# speaker-board.net
KiCad netlist of a schematic drawn in EAGLE
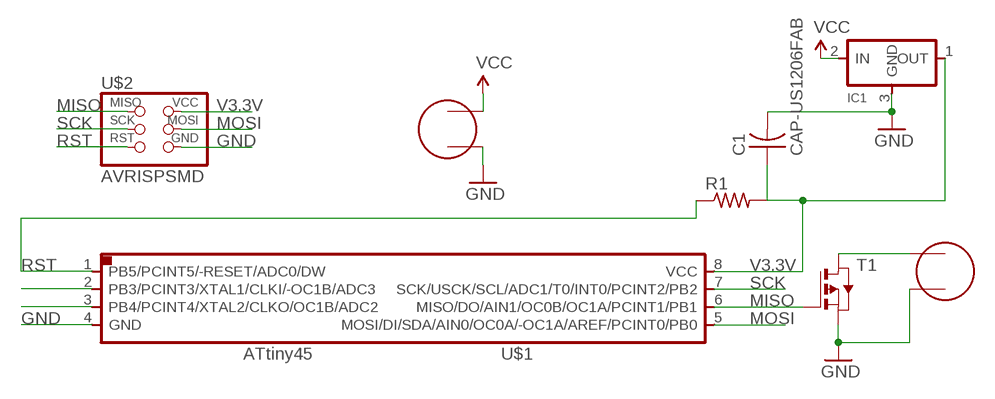
[diagram p0: schematic, sheet 1]

(export (version "E")
  (design (tool "Eeschema 10.0.6"))
  (components
    (comp (ref "C1")
      (value "CAP-US1206FAB")
      (footprint "eagle-import:C1206FAB")
      (libsource (lib "eagle-import") (part "CAP-US1206FAB"))
    )
    (comp (ref "IC1")
      (value "REGULATORSOT23")
      (footprint "eagle-import:SOT23")
      (libsource (lib "eagle-import") (part "REGULATORSOT23"))
    )
    (comp (ref "R1")
      (value "RES-US1206FAB")
      (footprint "eagle-import:R1206FAB")
      (libsource (lib "eagle-import") (part "RES-US1206FAB"))
    )
    (comp (ref "T1")
      (value "PMOSFETSOT23")
      (footprint "eagle-import:SOT-23")
      (libsource (lib "eagle-import") (part "PMOSFETSOT23"))
    )
    (comp (ref "U$1")
      (value "ATTINY45SI")
      (footprint "eagle-import:SOIC8")
      (libsource (lib "eagle-import") (part "ATTINY45SI"))
    )
    (comp (ref "U$2")
      (value "AVRISPSMD")
      (footprint "eagle-import:2X03SMD")
      (libsource (lib "eagle-import") (part "AVRISPSMD"))
    )
    (comp (ref "U$3")
      (value "PINHD-2X1-SMD")
      (footprint "eagle-import:2X01SMD")
      (libsource (lib "eagle-import") (part "PINHD-2X1-SMD"))
    )
    (comp (ref "U$4")
      (value "PINHD-2X1-SMD")
      (footprint "eagle-import:2X01SMD")
      (libsource (lib "eagle-import") (part "PINHD-2X1-SMD"))
    )
  )
  (nets
    (net (code "1") (name "/MISO") (class "Default")
      (node (ref "T1") (pin "3") (pinfunction "G_3") (pintype "passive"))
      (node (ref "U$1") (pin "6") (pinfunction "MISO/DO/AIN1/OC0B/OC1A/PCINT1/PB1_6") (pintype "bidirectional"))
      (node (ref "U$2") (pin "1") (pinfunction "MISO_1") (pintype "passive"))
    )
    (net (code "2") (name "/MOSI") (class "Default")
      (node (ref "U$1") (pin "5") (pinfunction "MOSI/DI/SDA/AIN0/OC0A/-OC1A/AREF/PCINT0/PB0_5") (pintype "bidirectional"))
      (node (ref "U$2") (pin "4") (pinfunction "MOSI_4") (pintype "passive"))
    )
    (net (code "3") (name "/RST") (class "Default")
      (node (ref "R1") (pin "1") (pinfunction "1_1") (pintype "passive"))
      (node (ref "U$1") (pin "1") (pinfunction "PB5/PCINT5/-RESET/ADC0/DW_1") (pintype "bidirectional"))
      (node (ref "U$2") (pin "5") (pinfunction "RST_5") (pintype "passive"))
    )
    (net (code "4") (name "/SCK") (class "Default")
      (node (ref "U$1") (pin "7") (pinfunction "SCK/USCK/SCL/ADC1/T0/INT0/PCINT2/PB2_7") (pintype "bidirectional"))
      (node (ref "U$2") (pin "3") (pinfunction "SCK_3") (pintype "passive"))
    )
    (net (code "5") (name "/V3.3V") (class "Default")
      (node (ref "C1") (pin "1") (pinfunction "1_1") (pintype "passive"))
      (node (ref "IC1") (pin "1") (pinfunction "OUT_1") (pintype "bidirectional"))
      (node (ref "R1") (pin "2") (pinfunction "2_2") (pintype "passive"))
      (node (ref "U$1") (pin "8") (pinfunction "VCC_8") (pintype "bidirectional"))
      (node (ref "U$2") (pin "2") (pinfunction "VCC_2") (pintype "passive"))
    )
    (net (code "6") (name "GND") (class "Default")
      (node (ref "C1") (pin "2") (pinfunction "2_2") (pintype "passive"))
      (node (ref "IC1") (pin "3") (pinfunction "GND_3") (pintype "bidirectional"))
      (node (ref "T1") (pin "2") (pinfunction "S_2") (pintype "passive"))
      (node (ref "U$1") (pin "4") (pinfunction "GND_4") (pintype "bidirectional"))
      (node (ref "U$2") (pin "6") (pinfunction "GND_6") (pintype "passive"))
      (node (ref "U$3") (pin "4") (pinfunction "P$2_4") (pintype "bidirectional"))
      (node (ref "U$4") (pin "3") (pinfunction "P$1_3") (pintype "bidirectional"))
    )
    (net (code "7") (name "Net-(T1-D)") (class "Default")
      (node (ref "T1") (pin "1") (pinfunction "D_1") (pintype "passive"))
      (node (ref "U$3") (pin "3") (pinfunction "P$1_3") (pintype "bidirectional"))
    )
    (net (code "8") (name "VCC") (class "Default")
      (node (ref "IC1") (pin "2") (pinfunction "IN_2") (pintype "bidirectional"))
      (node (ref "U$4") (pin "4") (pinfunction "P$2_4") (pintype "bidirectional"))
    )
    (net (code "9") (name "unconnected-(U$1-PB3{slash}PCINT3{slash}XTAL1{slash}CLKI{slash}-OC1B{slash}ADC3-Pad2)") (class "Default")
      (node (ref "U$1") (pin "2") (pinfunction "PB3/PCINT3/XTAL1/CLKI/-OC1B/ADC3_2") (pintype "bidirectional"))
    )
    (net (code "10") (name "unconnected-(U$1-PB4{slash}PCINT4{slash}XTAL2{slash}CLKO{slash}OC1B{slash}ADC2-Pad3)") (class "Default")
      (node (ref "U$1") (pin "3") (pinfunction "PB4/PCINT4/XTAL2/CLKO/OC1B/ADC2_3") (pintype "bidirectional"))
    )
  )
)
